# Microcontroller.net
KiCad netlist of a schematic drawn in Altium Designer
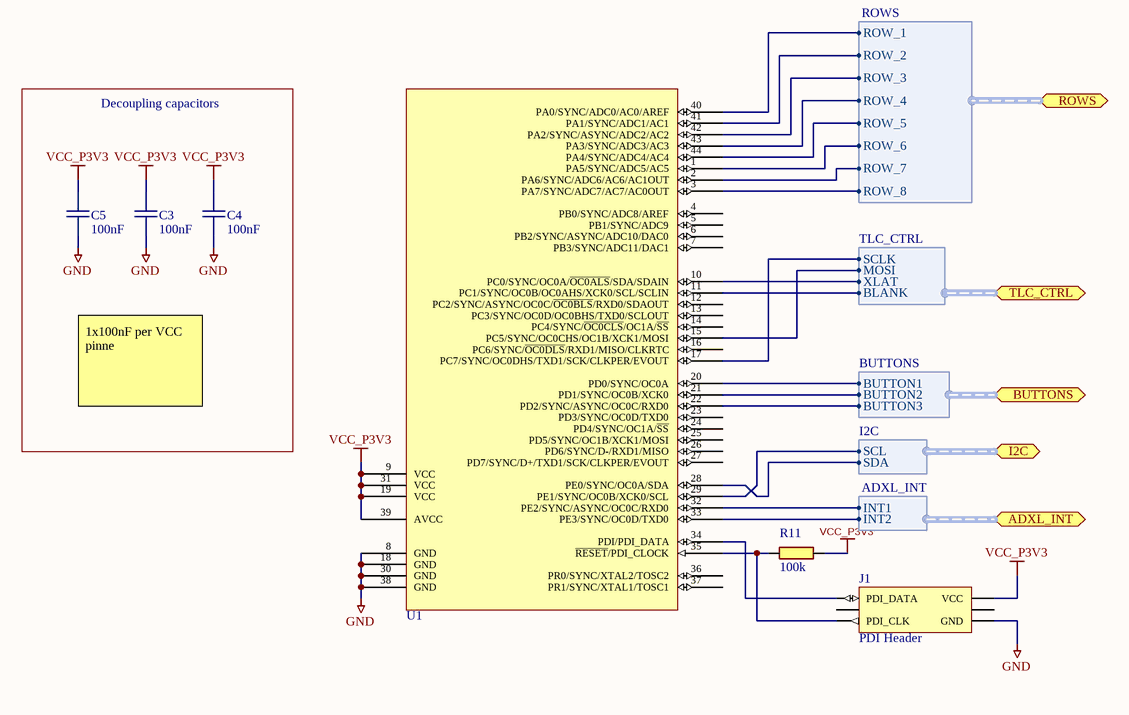
[diagram p0: Microcontroller.SchDoc]

(export (version "E")
  (design (tool "Eeschema 10.0.6"))
  (components
    (comp (ref "C3")
      (value "100nF")
      (footprint "CAPC0805(2012)100_N")
      (description "X7R 50V")
      (libsource (lib "OVLib") (part "CAP"))
    )
    (comp (ref "C4")
      (value "100nF")
      (footprint "CAPC0805(2012)100_N")
      (description "X7R 50V")
      (libsource (lib "OVLib") (part "CAP"))
    )
    (comp (ref "C5")
      (value "100nF")
      (footprint "CAPC0805(2012)100_N")
      (description "X7R 50V")
      (libsource (lib "OVLib") (part "CAP"))
    )
    (comp (ref "J1")
      (value "PDI Header")
      (footprint "HEADER_3x2")
      (description "PDI Xmega programming header")
      (libsource (lib "OVLib") (part "PDI-HEADER"))
    )
    (comp (ref "R11")
      (value "100k")
      (footprint "RESC0603(1608)_N")
      (description "0.1W 1% Thick film resistor")
      (libsource (lib "OVLib") (part "Resistor2"))
    )
    (comp (ref "U1")
      (value "ATXMEGA-A4U")
      (footprint "TQFP80P1200X1200X120-44N")
      (libsource (lib "OVLib") (part "ATXMEGA-A4U"))
    )
  )
  (nets
    (net (code "6") (name "/BLANK") (class "Default")
      (node (ref "U1") (pin "11") (pinfunction "PC1/SYNC/OC0B/OC0AHS/XCK0/SCL/SCLIN_11") (pintype "bidirectional"))
    )
    (net (code "7") (name "/BUTTON1") (class "Default")
      (node (ref "U1") (pin "20") (pinfunction "PD0/SYNC/OC0A_20") (pintype "bidirectional"))
    )
    (net (code "8") (name "/BUTTON2") (class "Default")
      (node (ref "U1") (pin "21") (pinfunction "PD1/SYNC/OC0B/XCK0_21") (pintype "bidirectional"))
    )
    (net (code "9") (name "/BUTTON3") (class "Default")
      (node (ref "U1") (pin "22") (pinfunction "PD2/SYNC/ASYNC/OC0C/RXD0_22") (pintype "bidirectional"))
    )
    (net (code "10") (name "/INT1") (class "Default")
      (node (ref "U1") (pin "32") (pinfunction "PE2/SYNC/ASYNC/OC0C/RXD0_32") (pintype "bidirectional"))
    )
    (net (code "11") (name "/INT2") (class "Default")
      (node (ref "U1") (pin "33") (pinfunction "PE3/SYNC/OC0D/TXD0_33") (pintype "bidirectional"))
    )
    (net (code "12") (name "/MOSI") (class "Default")
      (node (ref "U1") (pin "15") (pinfunction "PC5/SYNC/OC0CHS/OC1B/XCK1/MOSI_15") (pintype "bidirectional"))
    )
    (net (code "13") (name "/ROW_1") (class "Default")
      (node (ref "U1") (pin "40") (pinfunction "PA0/SYNC/ADC0/AC0/AREF_40") (pintype "bidirectional"))
    )
    (net (code "14") (name "/ROW_2") (class "Default")
      (node (ref "U1") (pin "41") (pinfunction "PA1/SYNC/ADC1/AC1_41") (pintype "bidirectional"))
    )
    (net (code "15") (name "/ROW_3") (class "Default")
      (node (ref "U1") (pin "42") (pinfunction "PA2/SYNC/ASYNC/ADC2/AC2_42") (pintype "bidirectional"))
    )
    (net (code "16") (name "/ROW_4") (class "Default")
      (node (ref "U1") (pin "43") (pinfunction "PA3/SYNC/ADC3/AC3_43") (pintype "bidirectional"))
    )
    (net (code "17") (name "/ROW_5") (class "Default")
      (node (ref "U1") (pin "44") (pinfunction "PA4/SYNC/ADC4/AC4_44") (pintype "bidirectional"))
    )
    (net (code "18") (name "/ROW_6") (class "Default")
      (node (ref "U1") (pin "1") (pinfunction "PA5/SYNC/ADC5/AC5_1") (pintype "bidirectional"))
    )
    (net (code "19") (name "/ROW_7") (class "Default")
      (node (ref "U1") (pin "2") (pinfunction "PA6/SYNC/ADC6/AC6/AC1OUT_2") (pintype "bidirectional"))
    )
    (net (code "20") (name "/ROW_8") (class "Default")
      (node (ref "U1") (pin "3") (pinfunction "PA7/SYNC/ADC7/AC7/AC0OUT_3") (pintype "bidirectional"))
    )
    (net (code "21") (name "/SCL") (class "Default")
      (node (ref "U1") (pin "29") (pinfunction "PE1/SYNC/OC0B/XCK0/SCL_29") (pintype "bidirectional"))
    )
    (net (code "22") (name "/SCLK") (class "Default")
      (node (ref "U1") (pin "17") (pinfunction "PC7/SYNC/OC0DHS/TXD1/SCK/CLKPER/EVOUT_17") (pintype "bidirectional"))
    )
    (net (code "23") (name "/SDA") (class "Default")
      (node (ref "U1") (pin "28") (pinfunction "PE0/SYNC/OC0A/SDA_28") (pintype "bidirectional"))
    )
    (net (code "24") (name "/XLAT") (class "Default")
      (node (ref "U1") (pin "10") (pinfunction "PC0/SYNC/OC0A/~{OC0ALS}/SDA/SDAIN_10") (pintype "bidirectional"))
    )
    (net (code "30") (name "GND") (class "Default")
      (node (ref "C3") (pin "1") (pinfunction "1_1") (pintype "passive"))
      (node (ref "C4") (pin "1") (pinfunction "1_1") (pintype "passive"))
      (node (ref "C5") (pin "1") (pinfunction "1_1") (pintype "passive"))
      (node (ref "J1") (pin "6") (pinfunction "GND_6") (pintype "power_in"))
      (node (ref "U1") (pin "18") (pinfunction "GND_18") (pintype "power_in"))
      (node (ref "U1") (pin "30") (pinfunction "GND_30") (pintype "power_in"))
      (node (ref "U1") (pin "38") (pinfunction "GND_38") (pintype "power_in"))
      (node (ref "U1") (pin "8") (pinfunction "GND_8") (pintype "power_in"))
    )
    (net (code "31") (name "Net-(J1-PDI_CLK)") (class "Default")
      (node (ref "J1") (pin "5") (pinfunction "PDI_CLK_5") (pintype "output"))
      (node (ref "R11") (pin "2") (pinfunction "2_2") (pintype "passive"))
      (node (ref "U1") (pin "35") (pinfunction "~{RESET}/PDI_CLOCK_35") (pintype "input"))
    )
    (net (code "32") (name "Net-(J1-PDI_DATA)") (class "Default")
      (node (ref "J1") (pin "1") (pinfunction "PDI_DATA_1") (pintype "bidirectional"))
      (node (ref "U1") (pin "34") (pinfunction "PDI/PDI_DATA_34") (pintype "bidirectional"))
    )
    (net (code "33") (name "VCC_P3V3") (class "Default")
      (node (ref "C3") (pin "2") (pinfunction "2_2") (pintype "passive"))
      (node (ref "C4") (pin "2") (pinfunction "2_2") (pintype "passive"))
      (node (ref "C5") (pin "2") (pinfunction "2_2") (pintype "passive"))
      (node (ref "J1") (pin "2") (pinfunction "VCC_2") (pintype "power_in"))
      (node (ref "R11") (pin "1") (pinfunction "1_1") (pintype "passive"))
      (node (ref "U1") (pin "19") (pinfunction "VCC_19") (pintype "power_in"))
      (node (ref "U1") (pin "31") (pinfunction "VCC_31") (pintype "power_in"))
      (node (ref "U1") (pin "39") (pinfunction "AVCC_39") (pintype "power_in"))
      (node (ref "U1") (pin "9") (pinfunction "VCC_9") (pintype "power_in"))
    )
    (net (code "34") (name "unconnected-(J1-Pad3)") (class "Default")
      (node (ref "J1") (pin "3") (pinfunction "3_3") (pintype "passive"))
    )
    (net (code "35") (name "unconnected-(J1-Pad4)") (class "Default")
      (node (ref "J1") (pin "4") (pinfunction "4_4") (pintype "passive"))
    )
    (net (code "36") (name "unconnected-(U1-PB0{slash}SYNC{slash}ADC8{slash}AREF-Pad4)") (class "Default")
      (node (ref "U1") (pin "4") (pinfunction "PB0/SYNC/ADC8/AREF_4") (pintype "bidirectional"))
    )
    (net (code "37") (name "unconnected-(U1-PB1{slash}SYNC{slash}ADC9-Pad5)") (class "Default")
      (node (ref "U1") (pin "5") (pinfunction "PB1/SYNC/ADC9_5") (pintype "bidirectional"))
    )
    (net (code "38") (name "unconnected-(U1-PB2{slash}SYNC{slash}ASYNC{slash}ADC10{slash}DAC0-Pad6)") (class "Default")
      (node (ref "U1") (pin "6") (pinfunction "PB2/SYNC/ASYNC/ADC10/DAC0_6") (pintype "bidirectional"))
    )
    (net (code "39") (name "unconnected-(U1-PB3{slash}SYNC{slash}ADC11{slash}DAC1-Pad7)") (class "Default")
      (node (ref "U1") (pin "7") (pinfunction "PB3/SYNC/ADC11/DAC1_7") (pintype "bidirectional"))
    )
    (net (code "40") (name "unconnected-(U1-PC2{slash}SYNC{slash}ASYNC{slash}OC0C{slash}~{OC0BLS}{slash}RXD0{slash}SDAOUT-Pad12)") (class "Default")
      (node (ref "U1") (pin "12") (pinfunction "PC2/SYNC/ASYNC/OC0C/~{OC0BLS}/RXD0/SDAOUT_12") (pintype "bidirectional"))
    )
    (net (code "41") (name "unconnected-(U1-PC3{slash}SYNC{slash}OC0D{slash}OC0BHS{slash}TXD0{slash}SCLOUT-Pad13)") (class "Default")
      (node (ref "U1") (pin "13") (pinfunction "PC3/SYNC/OC0D/OC0BHS/TXD0/SCLOUT_13") (pintype "bidirectional"))
    )
    (net (code "42") (name "unconnected-(U1-PC4{slash}SYNC{slash}~{OC0CLS}{slash}OC1A{slash}~{SS}-Pad14)") (class "Default")
      (node (ref "U1") (pin "14") (pinfunction "PC4/SYNC/~{OC0CLS}/OC1A/~{SS}_14") (pintype "bidirectional"))
    )
    (net (code "43") (name "unconnected-(U1-PC6{slash}SYNC{slash}~{OC0DLS}{slash}RXD1{slash}MISO{slash}CLKRTC-Pad16)") (class "Default")
      (node (ref "U1") (pin "16") (pinfunction "PC6/SYNC/~{OC0DLS}/RXD1/MISO/CLKRTC_16") (pintype "bidirectional"))
    )
    (net (code "44") (name "unconnected-(U1-PD3{slash}SYNC{slash}OC0D{slash}TXD0-Pad23)") (class "Default")
      (node (ref "U1") (pin "23") (pinfunction "PD3/SYNC/OC0D/TXD0_23") (pintype "bidirectional"))
    )
    (net (code "45") (name "unconnected-(U1-PD4{slash}SYNC{slash}OC1A{slash}~{SS}-Pad24)") (class "Default")
      (node (ref "U1") (pin "24") (pinfunction "PD4/SYNC/OC1A/~{SS}_24") (pintype "bidirectional"))
    )
    (net (code "46") (name "unconnected-(U1-PD5{slash}SYNC{slash}OC1B{slash}XCK1{slash}MOSI-Pad25)") (class "Default")
      (node (ref "U1") (pin "25") (pinfunction "PD5/SYNC/OC1B/XCK1/MOSI_25") (pintype "bidirectional"))
    )
    (net (code "47") (name "unconnected-(U1-PD6{slash}SYNC{slash}D-{slash}RXD1{slash}MISO-Pad26)") (class "Default")
      (node (ref "U1") (pin "26") (pinfunction "PD6/SYNC/D-/RXD1/MISO_26") (pintype "bidirectional"))
    )
    (net (code "48") (name "unconnected-(U1-PD7{slash}SYNC{slash}D+{slash}TXD1{slash}SCK{slash}CLKPER{slash}EVOUT-Pad27)") (class "Default")
      (node (ref "U1") (pin "27") (pinfunction "PD7/SYNC/D+/TXD1/SCK/CLKPER/EVOUT_27") (pintype "bidirectional"))
    )
    (net (code "49") (name "unconnected-(U1-PR0{slash}SYNC{slash}XTAL2{slash}TOSC2-Pad36)") (class "Default")
      (node (ref "U1") (pin "36") (pinfunction "PR0/SYNC/XTAL2/TOSC2_36") (pintype "bidirectional"))
    )
    (net (code "50") (name "unconnected-(U1-PR1{slash}SYNC{slash}XTAL1{slash}TOSC1-Pad37)") (class "Default")
      (node (ref "U1") (pin "37") (pinfunction "PR1/SYNC/XTAL1/TOSC1_37") (pintype "bidirectional"))
    )
  )
)
